# Main.net
KiCad netlist of a schematic drawn in Altium Designer
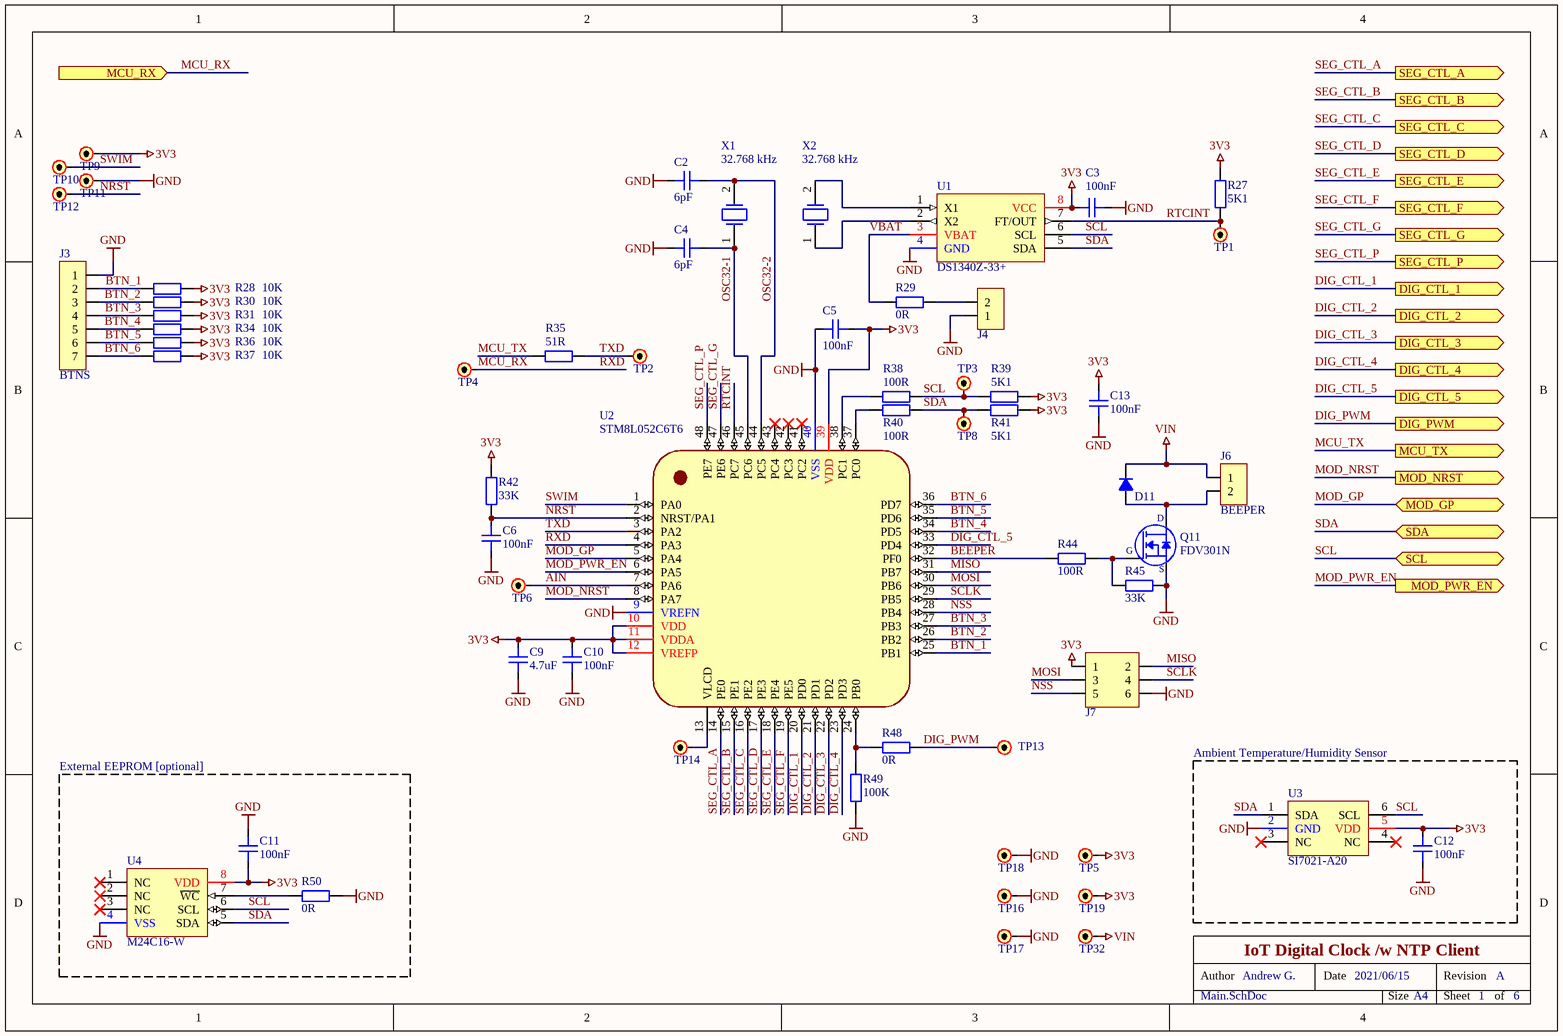
[diagram p0: Main.SchDoc]

(export (version "E")
  (design (tool "Eeschema 10.0.6"))
  (components
    (comp (ref "C2")
      (value "6pF")
      (footprint "0603C_RF_M")
      (description "Capacitor")
      (fields (field (name "TOLERANCE") "?") (field (name "MANUFACTURER") "Generic Brand"))
      (libsource (lib "AG.Generic") (part "C"))
    )
    (comp (ref "C3")
      (value "100nF")
      (footprint "0603C_RF_M")
      (description "Capacitor")
      (fields (field (name "TOLERANCE") "?") (field (name "MANUFACTURER") "Generic Brand"))
      (libsource (lib "AG.Generic") (part "C"))
    )
    (comp (ref "C4")
      (value "6pF")
      (footprint "0603C_RF_M")
      (description "Capacitor")
      (fields (field (name "TOLERANCE") "?") (field (name "MANUFACTURER") "Generic Brand"))
      (libsource (lib "AG.Generic") (part "C"))
    )
    (comp (ref "C5")
      (value "100nF")
      (footprint "0603C_RF_M")
      (description "Capacitor")
      (fields (field (name "TOLERANCE") "?") (field (name "MANUFACTURER") "Generic Brand"))
      (libsource (lib "AG.Generic") (part "C"))
    )
    (comp (ref "C6")
      (value "100nF")
      (footprint "0603C_RF_M")
      (description "Capacitor")
      (fields (field (name "TOLERANCE") "?") (field (name "MANUFACTURER") "Generic Brand"))
      (libsource (lib "AG.Generic") (part "C"))
    )
    (comp (ref "C9")
      (value "4.7uF")
      (footprint "0603C_RF_M")
      (description "Capacitor")
      (fields (field (name "TOLERANCE") "?") (field (name "MANUFACTURER") "Generic Brand"))
      (libsource (lib "AG.Generic") (part "C"))
    )
    (comp (ref "C10")
      (value "100nF")
      (footprint "0603C_RF_M")
      (description "Capacitor")
      (fields (field (name "TOLERANCE") "?") (field (name "MANUFACTURER") "Generic Brand"))
      (libsource (lib "AG.Generic") (part "C"))
    )
    (comp (ref "C11")
      (value "100nF")
      (footprint "0603C_RF_M")
      (description "Capacitor")
      (fields (field (name "TOLERANCE") "?") (field (name "MANUFACTURER") "Generic Brand"))
      (libsource (lib "AG.Generic") (part "C"))
    )
    (comp (ref "C12")
      (value "100nF")
      (footprint "0603C_RF_M")
      (description "Capacitor")
      (fields (field (name "TOLERANCE") "?") (field (name "MANUFACTURER") "Generic Brand"))
      (libsource (lib "AG.Generic") (part "C"))
    )
    (comp (ref "C13")
      (value "100nF")
      (footprint "0805C_RF_M")
      (description "Capacitor")
      (fields (field (name "TOLERANCE") "?") (field (name "MANUFACTURER") "Generic Brand"))
      (libsource (lib "AG.Generic") (part "C"))
    )
    (comp (ref "D11")
      (value "D")
      (footprint "ONSEMI_DO214AC_RF_M")
      (description "Diode (Rectifier)")
      (fields (field (name "MANUFACTURER") "Generic Brand"))
      (libsource (lib "AG.Generic") (part "D"))
    )
    (comp (ref "J3")
      (value "BTNS")
      (footprint "HEADER-2.54-7P1")
      (description "Pin Header Single Row 7 Positions")
      (libsource (lib "AG.Connectors") (part "PINHDR-7P1"))
    )
    (comp (ref "J4")
      (value "PINHDR-2P1")
      (footprint "HEADER-2.54-2P1")
      (description "Pin Header Single Row 2 Positions")
      (libsource (lib "") (part "PINHDR-2P1_1"))
    )
    (comp (ref "J6")
      (value "BEEPER")
      (footprint "HEADER-2.54-2P1")
      (description "Pin Header Single Row 2 Positions")
      (libsource (lib "AG.Connectors") (part "PINHDR-2P1"))
    )
    (comp (ref "J7")
      (value "PINHDR-6P2-2.54")
      (footprint "HEADER-2.54-6P-2R")
      (description "Rectangular Pin Header 6 Positions 2 Rows")
      (libsource (lib "AG.Connectors") (part "PINHDR-6P2-2.54"))
    )
    (comp (ref "Q11")
      (value "FDV301N")
      (footprint "IRLML_SOT-23")
      (description "MOSFET N-CH 25V 220MA SOT23")
      (fields
        (field (name "MANUFACTURER") "ON Semiconductor")
        (field (name "ALTERNATIVE SUPPLIER PART NO") "9010000157")
      )
      (libsource (lib "AG.Discrete") (part "FDV301N"))
    )
    (comp (ref "R27")
      (value "5K1")
      (footprint "0603R_RF_M")
      (description "Resistor")
      (fields (field (name "TOLERANCE") "?") (field (name "MANUFACTURER") "Generic Brand"))
      (libsource (lib "AG.Generic") (part "R"))
    )
    (comp (ref "R28")
      (value "10K")
      (footprint "0603R_RF_M")
      (description "Resistor")
      (fields (field (name "TOLERANCE") "?") (field (name "MANUFACTURER") "Generic Brand"))
      (libsource (lib "AG.Generic") (part "R"))
    )
    (comp (ref "R29")
      (value "0R")
      (footprint "0805R_RF_M")
      (description "Resistor")
      (fields (field (name "TOLERANCE") "?") (field (name "MANUFACTURER") "Generic Brand"))
      (libsource (lib "") (part "R_1"))
    )
    (comp (ref "R30")
      (value "10K")
      (footprint "0603R_RF_M")
      (description "Resistor")
      (fields (field (name "TOLERANCE") "?") (field (name "MANUFACTURER") "Generic Brand"))
      (libsource (lib "AG.Generic") (part "R"))
    )
    (comp (ref "R31")
      (value "10K")
      (footprint "0603R_RF_M")
      (description "Resistor")
      (fields (field (name "TOLERANCE") "?") (field (name "MANUFACTURER") "Generic Brand"))
      (libsource (lib "AG.Generic") (part "R"))
    )
    (comp (ref "R34")
      (value "10K")
      (footprint "0603R_RF_M")
      (description "Resistor")
      (fields (field (name "TOLERANCE") "?") (field (name "MANUFACTURER") "Generic Brand"))
      (libsource (lib "AG.Generic") (part "R"))
    )
    (comp (ref "R35")
      (value "51R")
      (footprint "0603R_RF_M")
      (description "Resistor")
      (fields (field (name "TOLERANCE") "?") (field (name "MANUFACTURER") "Generic Brand"))
      (libsource (lib "AG.Generic") (part "R"))
    )
    (comp (ref "R36")
      (value "10K")
      (footprint "0603R_RF_M")
      (description "Resistor")
      (fields (field (name "TOLERANCE") "?") (field (name "MANUFACTURER") "Generic Brand"))
      (libsource (lib "AG.Generic") (part "R"))
    )
    (comp (ref "R37")
      (value "10K")
      (footprint "0603R_RF_M")
      (description "Resistor")
      (fields (field (name "TOLERANCE") "?") (field (name "MANUFACTURER") "Generic Brand"))
      (libsource (lib "AG.Generic") (part "R"))
    )
    (comp (ref "R38")
      (value "100R")
      (footprint "0603R_RF_M")
      (description "Resistor")
      (fields (field (name "TOLERANCE") "?") (field (name "MANUFACTURER") "Generic Brand"))
      (libsource (lib "AG.Generic") (part "R"))
    )
    (comp (ref "R39")
      (value "5K1")
      (footprint "0805R_RF_M")
      (description "Resistor")
      (fields (field (name "TOLERANCE") "?") (field (name "MANUFACTURER") "Generic Brand"))
      (libsource (lib "") (part "R_1"))
    )
    (comp (ref "R40")
      (value "100R")
      (footprint "0603R_RF_M")
      (description "Resistor")
      (fields (field (name "TOLERANCE") "?") (field (name "MANUFACTURER") "Generic Brand"))
      (libsource (lib "AG.Generic") (part "R"))
    )
    (comp (ref "R41")
      (value "5K1")
      (footprint "0805R_RF_M")
      (description "Resistor")
      (fields (field (name "TOLERANCE") "?") (field (name "MANUFACTURER") "Generic Brand"))
      (libsource (lib "") (part "R_1"))
    )
    (comp (ref "R42")
      (value "33K")
      (footprint "0603R_RF_M")
      (description "Resistor")
      (fields (field (name "TOLERANCE") "?") (field (name "MANUFACTURER") "Generic Brand"))
      (libsource (lib "AG.Generic") (part "R"))
    )
    (comp (ref "R44")
      (value "100R")
      (footprint "0805R_RF_M")
      (description "Resistor")
      (fields (field (name "TOLERANCE") "?") (field (name "MANUFACTURER") "Generic Brand"))
      (libsource (lib "") (part "R_1"))
    )
    (comp (ref "R45")
      (value "33K")
      (footprint "0805R_RF_M")
      (description "Resistor")
      (fields (field (name "TOLERANCE") "?") (field (name "MANUFACTURER") "Generic Brand"))
      (libsource (lib "") (part "R_1"))
    )
    (comp (ref "R48")
      (value "0R")
      (footprint "0603R_RF_M")
      (description "Resistor")
      (fields (field (name "TOLERANCE") "?") (field (name "MANUFACTURER") "Generic Brand"))
      (libsource (lib "AG.Generic") (part "R"))
    )
    (comp (ref "R49")
      (value "100K")
      (footprint "0603R_RF_M")
      (description "Resistor")
      (fields (field (name "TOLERANCE") "?") (field (name "MANUFACTURER") "Generic Brand"))
      (libsource (lib "AG.Generic") (part "R"))
    )
    (comp (ref "R50")
      (value "0R")
      (footprint "0603R_RF_M")
      (description "Resistor")
      (fields (field (name "TOLERANCE") "?") (field (name "MANUFACTURER") "Generic Brand"))
      (libsource (lib "AG.Generic") (part "R"))
    )
    (comp (ref "TP1")
      (value "RTCINT")
      (footprint "PAD_R_1MM")
      (description "Test Point / Pad")
      (libsource (lib "AG.Misc") (part "Test Point"))
    )
    (comp (ref "TP2")
      (value "MCU_TX")
      (footprint "PAD_R_1MM")
      (description "Test Point / Pad")
      (libsource (lib "AG.Misc") (part "Test Point"))
    )
    (comp (ref "TP3")
      (value "SCL")
      (footprint "PAD_R_1MM")
      (description "Test Point / Pad")
      (libsource (lib "AG.Misc") (part "Test Point"))
    )
    (comp (ref "TP4")
      (value "MCU_RX")
      (footprint "PAD_R_1MM")
      (description "Test Point / Pad")
      (libsource (lib "AG.Misc") (part "Test Point"))
    )
    (comp (ref "TP5")
      (value "3V3")
      (footprint "PAD_R_1.5MM")
      (description "Test Point / Pad")
      (libsource (lib "AG.Misc") (part "Test Point"))
    )
    (comp (ref "TP6")
      (value "3V3")
      (footprint "PAD_R_1MM")
      (description "Test Point / Pad")
      (libsource (lib "AG.Misc") (part "Test Point"))
    )
    (comp (ref "TP8")
      (value "SDA")
      (footprint "PAD_R_1MM")
      (description "Test Point / Pad")
      (libsource (lib "AG.Misc") (part "Test Point"))
    )
    (comp (ref "TP9")
      (value "VDD")
      (footprint "PAD_R_1MM")
      (description "Test Point / Pad")
      (libsource (lib "AG.Misc") (part "Test Point"))
    )
    (comp (ref "TP10")
      (value "SWIM")
      (footprint "PAD_R_1MM")
      (description "Test Point / Pad")
      (libsource (lib "AG.Misc") (part "Test Point"))
    )
    (comp (ref "TP11")
      (value "GND")
      (footprint "PAD_R_1MM")
      (description "Test Point / Pad")
      (libsource (lib "AG.Misc") (part "Test Point"))
    )
    (comp (ref "TP12")
      (value "NRST")
      (footprint "PAD_R_1MM")
      (description "Test Point / Pad")
      (libsource (lib "AG.Misc") (part "Test Point"))
    )
    (comp (ref "TP13")
      (value "PWM")
      (footprint "PAD_R_1MM")
      (description "Test Point / Pad")
      (libsource (lib "AG.Misc") (part "Test Point"))
    )
    (comp (ref "TP14")
      (value "VLCD")
      (footprint "PAD_R_1MM")
      (description "Test Point / Pad")
      (libsource (lib "AG.Misc") (part "Test Point"))
    )
    (comp (ref "TP16")
      (value "GND")
      (footprint "PAD_R_1.5MM")
      (description "Test Point / Pad")
      (libsource (lib "AG.Misc") (part "Test Point"))
    )
    (comp (ref "TP17")
      (value "GND")
      (footprint "PAD_R_1.5MM")
      (description "Test Point / Pad")
      (libsource (lib "AG.Misc") (part "Test Point"))
    )
    (comp (ref "TP18")
      (value "GND")
      (footprint "PAD_R_1.5MM")
      (description "Test Point / Pad")
      (libsource (lib "AG.Misc") (part "Test Point"))
    )
    (comp (ref "TP19")
      (value "3V3")
      (footprint "PAD_R_1.5MM")
      (description "Test Point / Pad")
      (libsource (lib "AG.Misc") (part "Test Point"))
    )
    (comp (ref "TP32")
      (value "VIN")
      (footprint "PAD_R_1.5MM")
      (description "Test Point / Pad")
      (libsource (lib "AG.Misc") (part "Test Point"))
    )
    (comp (ref "U1")
      (value "DS1340Z-33+")
      (footprint "SOIC-8")
      (description "IC RTC CLK/CALENDAR I2C 8-SOIC")
      (fields
        (field (name "MANUFACTURER") "Maxim Integrated")
        (field (name "ALTERNATIVE SUPPLIER PART NO") "9000387657")
      )
      (libsource (lib "AG.IC") (part "DS1340Z-33+"))
    )
    (comp (ref "U2")
      (value "STM8L052C6T6")
      (footprint "ST_LQFP-48")
      (description "IC MCU 8BIT 32KB FLASH 48LQFP")
      (fields (field (name "MANUFACTURER") "STMicroelectronics"))
      (libsource (lib "AG.MCU") (part "STM8L052C6T6"))
    )
    (comp (ref "U3")
      (value "SI7021-A20")
      (footprint "SI7021_DFN-6_RF_M")
      (description "SENS HUMID/TEMP 3.6V I2C 2% 6DFN")
      (fields (field (name "MANUFACTURER") "Silicon Labs"))
      (libsource (lib "AG.IC") (part "SI7021-A20"))
    )
    (comp (ref "U4")
      (value "M24C16-W")
      (footprint "SOIC-8")
      (description "IC SRL EEPROM 16KBIT 2.5V 8-SOIC")
      (fields (field (name "MANUFACTURER") "STMicroelectronics"))
      (libsource (lib "AG.IC") (part "M24C16-W"))
    )
    (comp (ref "X1")
      (value "32.768 kHz")
      (footprint "XTAL_3215")
      (description "Crystal Resonator (2 Leads)")
      (fields (field (name "MANUFACTURER") "Geyer") (field (name "MANUFACTURER PART NO") "KX-327NHT"))
      (libsource (lib "AG.Passive") (part "KX-327NHT"))
    )
    (comp (ref "X2")
      (value "32.768 kHz")
      (footprint "XTAL_3215")
      (description "Crystal Resonator (2 Leads)")
      (fields (field (name "MANUFACTURER") "Geyer") (field (name "MANUFACTURER PART NO") "KX-327NHT"))
      (libsource (lib "AG.Passive") (part "KX-327NHT"))
    )
  )
  (nets
    (net (code "1") (name "/AIN") (class "Default")
      (node (ref "TP6") (pin "1") (pinfunction "1_1") (pintype "passive"))
      (node (ref "U2") (pin "7") (pinfunction "PA6_7") (pintype "bidirectional"))
    )
    (net (code "2") (name "/BEEPER") (class "Default")
      (node (ref "R44") (pin "1") (pintype "passive"))
      (node (ref "U2") (pin "32") (pinfunction "PF0_32") (pintype "bidirectional"))
    )
    (net (code "3") (name "/BTN_1") (class "Default")
      (node (ref "J3") (pin "2") (pinfunction "2_2") (pintype "passive"))
      (node (ref "R28") (pin "1") (pintype "passive"))
      (node (ref "U2") (pin "25") (pinfunction "PB1_25") (pintype "bidirectional"))
    )
    (net (code "4") (name "/BTN_2") (class "Default")
      (node (ref "J3") (pin "3") (pinfunction "3_3") (pintype "passive"))
      (node (ref "R30") (pin "1") (pintype "passive"))
      (node (ref "U2") (pin "26") (pinfunction "PB2_26") (pintype "bidirectional"))
    )
    (net (code "5") (name "/BTN_3") (class "Default")
      (node (ref "J3") (pin "4") (pinfunction "4_4") (pintype "passive"))
      (node (ref "R31") (pin "1") (pintype "passive"))
      (node (ref "U2") (pin "27") (pinfunction "PB3_27") (pintype "bidirectional"))
    )
    (net (code "6") (name "/BTN_4") (class "Default")
      (node (ref "J3") (pin "5") (pinfunction "5_5") (pintype "passive"))
      (node (ref "R34") (pin "1") (pintype "passive"))
      (node (ref "U2") (pin "34") (pinfunction "PD5_34") (pintype "bidirectional"))
    )
    (net (code "7") (name "/BTN_5") (class "Default")
      (node (ref "J3") (pin "6") (pinfunction "6_6") (pintype "passive"))
      (node (ref "R36") (pin "1") (pintype "passive"))
      (node (ref "U2") (pin "35") (pinfunction "PD6_35") (pintype "bidirectional"))
    )
    (net (code "8") (name "/BTN_6") (class "Default")
      (node (ref "J3") (pin "7") (pinfunction "7_7") (pintype "passive"))
      (node (ref "R37") (pin "1") (pintype "passive"))
      (node (ref "U2") (pin "36") (pinfunction "PD7_36") (pintype "bidirectional"))
    )
    (net (code "9") (name "/DIG_CTL_1") (class "Default")
      (node (ref "U2") (pin "20") (pinfunction "PD0_20") (pintype "bidirectional"))
    )
    (net (code "10") (name "/DIG_CTL_2") (class "Default")
      (node (ref "U2") (pin "21") (pinfunction "PD1_21") (pintype "bidirectional"))
    )
    (net (code "11") (name "/DIG_CTL_3") (class "Default")
      (node (ref "U2") (pin "22") (pinfunction "PD2_22") (pintype "bidirectional"))
    )
    (net (code "12") (name "/DIG_CTL_4") (class "Default")
      (node (ref "U2") (pin "23") (pinfunction "PD3_23") (pintype "bidirectional"))
    )
    (net (code "13") (name "/DIG_CTL_5") (class "Default")
      (node (ref "U2") (pin "33") (pinfunction "PD4_33") (pintype "bidirectional"))
    )
    (net (code "14") (name "/DIG_PWM") (class "Default")
      (node (ref "R48") (pin "1") (pintype "passive"))
      (node (ref "TP13") (pin "1") (pinfunction "1_1") (pintype "passive"))
    )
    (net (code "15") (name "/MCU_RX") (class "Default")
      (node (ref "TP4") (pin "1") (pinfunction "1_1") (pintype "passive"))
      (node (ref "U2") (pin "4") (pinfunction "PA3_4") (pintype "bidirectional"))
    )
    (net (code "16") (name "/MCU_TX") (class "Default") (node (ref "R35") (pin "1") (pintype "passive")))
    (net (code "17") (name "/MISO") (class "Default")
      (node (ref "J7") (pin "2") (pinfunction "2_2") (pintype "passive"))
      (node (ref "U2") (pin "31") (pinfunction "PB7_31") (pintype "bidirectional"))
    )
    (net (code "18") (name "/MOD_GP") (class "Default")
      (node (ref "U2") (pin "5") (pinfunction "PA4_5") (pintype "bidirectional"))
    )
    (net (code "19") (name "/MOD_NRST") (class "Default")
      (node (ref "U2") (pin "8") (pinfunction "PA7_8") (pintype "bidirectional"))
    )
    (net (code "20") (name "/MOD_PWR_EN") (class "Default")
      (node (ref "U2") (pin "6") (pinfunction "PA5_6") (pintype "bidirectional"))
    )
    (net (code "21") (name "/MOSI") (class "Default")
      (node (ref "J7") (pin "3") (pinfunction "3_3") (pintype "passive"))
      (node (ref "U2") (pin "30") (pinfunction "PB6_30") (pintype "bidirectional"))
    )
    (net (code "22") (name "/NRST") (class "Default")
      (node (ref "C6") (pin "2") (pinfunction "2_2") (pintype "passive"))
      (node (ref "R42") (pin "1") (pintype "passive"))
      (node (ref "TP12") (pin "1") (pinfunction "1_1") (pintype "passive"))
      (node (ref "U2") (pin "2") (pinfunction "NRST/PA1_2") (pintype "bidirectional"))
    )
    (net (code "23") (name "/NSS") (class "Default")
      (node (ref "J7") (pin "5") (pinfunction "5_5") (pintype "passive"))
      (node (ref "U2") (pin "28") (pinfunction "PB4_28") (pintype "bidirectional"))
    )
    (net (code "24") (name "/OSC32-1") (class "Default")
      (node (ref "C4") (pin "1") (pinfunction "1_1") (pintype "passive"))
      (node (ref "U2") (pin "45") (pinfunction "PC6_45") (pintype "bidirectional"))
      (node (ref "X1") (pin "1") (pinfunction "1_1") (pintype "passive"))
    )
    (net (code "25") (name "/OSC32-2") (class "Default")
      (node (ref "C2") (pin "1") (pinfunction "1_1") (pintype "passive"))
      (node (ref "U2") (pin "44") (pinfunction "PC5_44") (pintype "bidirectional"))
      (node (ref "X1") (pin "2") (pinfunction "2_2") (pintype "passive"))
    )
    (net (code "26") (name "/RTCINT") (class "Default")
      (node (ref "R27") (pin "1") (pintype "passive"))
      (node (ref "TP1") (pin "1") (pinfunction "1_1") (pintype "passive"))
      (node (ref "U1") (pin "7") (pinfunction "FT/OUT_7") (pintype "output"))
      (node (ref "U2") (pin "46") (pinfunction "PC7_46") (pintype "bidirectional"))
    )
    (net (code "27") (name "/SCL") (class "Default")
      (node (ref "R38") (pin "2") (pintype "passive"))
      (node (ref "R39") (pin "1") (pintype "passive"))
      (node (ref "TP3") (pin "1") (pinfunction "1_1") (pintype "passive"))
      (node (ref "U1") (pin "6") (pinfunction "SCL_6") (pintype "open_collector"))
      (node (ref "U3") (pin "6") (pinfunction "SCL_6") (pintype "passive"))
      (node (ref "U4") (pin "6") (pinfunction "SCL_6") (pintype "bidirectional"))
    )
    (net (code "28") (name "/SCLK") (class "Default")
      (node (ref "J7") (pin "4") (pinfunction "4_4") (pintype "passive"))
      (node (ref "U2") (pin "29") (pinfunction "PB5_29") (pintype "bidirectional"))
    )
    (net (code "29") (name "/SDA") (class "Default")
      (node (ref "R40") (pin "2") (pintype "passive"))
      (node (ref "R41") (pin "1") (pintype "passive"))
      (node (ref "TP8") (pin "1") (pinfunction "1_1") (pintype "passive"))
      (node (ref "U1") (pin "5") (pinfunction "SDA_5") (pintype "open_collector"))
      (node (ref "U3") (pin "1") (pinfunction "SDA_1") (pintype "passive"))
      (node (ref "U4") (pin "5") (pinfunction "SDA_5") (pintype "bidirectional"))
    )
    (net (code "30") (name "/SEG_CTL_A") (class "Default")
      (node (ref "U2") (pin "14") (pinfunction "PE0_14") (pintype "bidirectional"))
    )
    (net (code "31") (name "/SEG_CTL_B") (class "Default")
      (node (ref "U2") (pin "15") (pinfunction "PE1_15") (pintype "bidirectional"))
    )
    (net (code "32") (name "/SEG_CTL_C") (class "Default")
      (node (ref "U2") (pin "16") (pinfunction "PE2_16") (pintype "bidirectional"))
    )
    (net (code "33") (name "/SEG_CTL_D") (class "Default")
      (node (ref "U2") (pin "17") (pinfunction "PE3_17") (pintype "bidirectional"))
    )
    (net (code "34") (name "/SEG_CTL_E") (class "Default")
      (node (ref "U2") (pin "18") (pinfunction "PE4_18") (pintype "bidirectional"))
    )
    (net (code "35") (name "/SEG_CTL_F") (class "Default")
      (node (ref "U2") (pin "19") (pinfunction "PE5_19") (pintype "bidirectional"))
    )
    (net (code "36") (name "/SEG_CTL_G") (class "Default")
      (node (ref "U2") (pin "47") (pinfunction "PE6_47") (pintype "bidirectional"))
    )
    (net (code "37") (name "/SEG_CTL_P") (class "Default")
      (node (ref "U2") (pin "48") (pinfunction "PE7_48") (pintype "bidirectional"))
    )
    (net (code "38") (name "/SWIM") (class "Default")
      (node (ref "TP10") (pin "1") (pinfunction "1_1") (pintype "passive"))
      (node (ref "U2") (pin "1") (pinfunction "PA0_1") (pintype "bidirectional"))
    )
    (net (code "39") (name "/TXD") (class "Default")
      (node (ref "R35") (pin "2") (pintype "passive"))
      (node (ref "TP2") (pin "1") (pinfunction "1_1") (pintype "passive"))
      (node (ref "U2") (pin "3") (pinfunction "PA2_3") (pintype "bidirectional"))
    )
    (net (code "40") (name "/VBAT") (class "Default")
      (node (ref "R29") (pin "2") (pintype "passive"))
      (node (ref "U1") (pin "3") (pinfunction "VBAT_3") (pintype "power_in"))
    )
    (net (code "41") (name "3V3") (class "Default")
      (node (ref "C10") (pin "2") (pinfunction "2_2") (pintype "passive"))
      (node (ref "C11") (pin "2") (pinfunction "2_2") (pintype "passive"))
      (node (ref "C12") (pin "2") (pinfunction "2_2") (pintype "passive"))
      (node (ref "C13") (pin "2") (pinfunction "2_2") (pintype "passive"))
      (node (ref "C3") (pin "2") (pinfunction "2_2") (pintype "passive"))
      (node (ref "C5") (pin "1") (pinfunction "1_1") (pintype "passive"))
      (node (ref "C9") (pin "2") (pinfunction "2_2") (pintype "passive"))
      (node (ref "J7") (pin "1") (pinfunction "1_1") (pintype "passive"))
      (node (ref "R27") (pin "2") (pintype "passive"))
      (node (ref "R28") (pin "2") (pintype "passive"))
      (node (ref "R30") (pin "2") (pintype "passive"))
      (node (ref "R31") (pin "2") (pintype "passive"))
      (node (ref "R34") (pin "2") (pintype "passive"))
      (node (ref "R36") (pin "2") (pintype "passive"))
      (node (ref "R37") (pin "2") (pintype "passive"))
      (node (ref "R39") (pin "2") (pintype "passive"))
      (node (ref "R41") (pin "2") (pintype "passive"))
      (node (ref "R42") (pin "2") (pintype "passive"))
      (node (ref "TP19") (pin "1") (pinfunction "1_1") (pintype "passive"))
      (node (ref "TP5") (pin "1") (pinfunction "1_1") (pintype "passive"))
      (node (ref "TP9") (pin "1") (pinfunction "1_1") (pintype "passive"))
      (node (ref "U1") (pin "8") (pinfunction "VCC_8") (pintype "power_in"))
      (node (ref "U2") (pin "10") (pinfunction "VDD_10") (pintype "power_in"))
      (node (ref "U2") (pin "11") (pinfunction "VDDA_11") (pintype "power_in"))
      (node (ref "U2") (pin "12") (pinfunction "VREFP_12") (pintype "power_in"))
      (node (ref "U2") (pin "39") (pinfunction "VDD_39") (pintype "power_in"))
      (node (ref "U3") (pin "5") (pinfunction "VDD_5") (pintype "passive"))
      (node (ref "U4") (pin "8") (pinfunction "VDD_8") (pintype "power_in"))
    )
    (net (code "42") (name "GND") (class "Default")
      (node (ref "C10") (pin "1") (pinfunction "1_1") (pintype "passive"))
      (node (ref "C11") (pin "1") (pinfunction "1_1") (pintype "passive"))
      (node (ref "C12") (pin "1") (pinfunction "1_1") (pintype "passive"))
      (node (ref "C13") (pin "1") (pinfunction "1_1") (pintype "passive"))
      (node (ref "C2") (pin "2") (pinfunction "2_2") (pintype "passive"))
      (node (ref "C3") (pin "1") (pinfunction "1_1") (pintype "passive"))
      (node (ref "C4") (pin "2") (pinfunction "2_2") (pintype "passive"))
      (node (ref "C5") (pin "2") (pinfunction "2_2") (pintype "passive"))
      (node (ref "C6") (pin "1") (pinfunction "1_1") (pintype "passive"))
      (node (ref "C9") (pin "1") (pinfunction "1_1") (pintype "passive"))
      (node (ref "J3") (pin "1") (pinfunction "1_1") (pintype "passive"))
      (node (ref "J4") (pin "1") (pinfunction "1_1") (pintype "passive"))
      (node (ref "J7") (pin "6") (pinfunction "6_6") (pintype "passive"))
      (node (ref "Q11") (pin "2") (pinfunction "S_2") (pintype "passive"))
      (node (ref "R45") (pin "1") (pintype "passive"))
      (node (ref "R49") (pin "2") (pintype "passive"))
      (node (ref "R50") (pin "2") (pintype "passive"))
      (node (ref "TP11") (pin "1") (pinfunction "1_1") (pintype "passive"))
      (node (ref "TP16") (pin "1") (pinfunction "1_1") (pintype "passive"))
      (node (ref "TP17") (pin "1") (pinfunction "1_1") (pintype "passive"))
      (node (ref "TP18") (pin "1") (pinfunction "1_1") (pintype "passive"))
      (node (ref "U1") (pin "4") (pinfunction "GND_4") (pintype "power_in"))
      (node (ref "U2") (pin "40") (pinfunction "VSS_40") (pintype "power_in"))
      (node (ref "U2") (pin "9") (pinfunction "VREFN_9") (pintype "power_in"))
      (node (ref "U3") (pin "2") (pinfunction "GND_2") (pintype "passive"))
      (node (ref "U4") (pin "4") (pinfunction "VSS_4") (pintype "power_in"))
    )
    (net (code "43") (name "Net-(J4-Pad2)") (class "Default")
      (node (ref "J4") (pin "2") (pinfunction "2_2") (pintype "passive"))
      (node (ref "R29") (pin "1") (pintype "passive"))
    )
    (net (code "44") (name "Net-(Q11-D)") (class "Default")
      (node (ref "D11") (pin "A") (pinfunction "A_A") (pintype "passive"))
      (node (ref "J6") (pin "2") (pinfunction "2_2") (pintype "passive"))
      (node (ref "Q11") (pin "3") (pinfunction "D_3") (pintype "passive"))
    )
    (net (code "45") (name "Net-(Q11-G)") (class "Default")
      (node (ref "Q11") (pin "1") (pinfunction "G_1") (pintype "passive"))
      (node (ref "R44") (pin "2") (pintype "passive"))
      (node (ref "R45") (pin "2") (pintype "passive"))
    )
    (net (code "46") (name "Net-(U1-X1)") (class "Default")
      (node (ref "U1") (pin "1") (pinfunction "X1_1") (pintype "input"))
      (node (ref "X2") (pin "2") (pinfunction "2_2") (pintype "passive"))
    )
    (net (code "47") (name "Net-(U1-X2)") (class "Default")
      (node (ref "U1") (pin "2") (pinfunction "X2_2") (pintype "output"))
      (node (ref "X2") (pin "1") (pinfunction "1_1") (pintype "passive"))
    )
    (net (code "48") (name "Net-(U2-PB0)") (class "Default")
      (node (ref "R48") (pin "2") (pintype "passive"))
      (node (ref "R49") (pin "1") (pintype "passive"))
      (node (ref "U2") (pin "24") (pinfunction "PB0_24") (pintype "bidirectional"))
    )
    (net (code "49") (name "Net-(U2-PC0)") (class "Default")
      (node (ref "R40") (pin "1") (pintype "passive"))
      (node (ref "U2") (pin "37") (pinfunction "PC0_37") (pintype "bidirectional"))
    )
    (net (code "50") (name "Net-(U2-PC1)") (class "Default")
      (node (ref "R38") (pin "1") (pintype "passive"))
      (node (ref "U2") (pin "38") (pinfunction "PC1_38") (pintype "bidirectional"))
    )
    (net (code "51") (name "Net-(U2-VLCD)") (class "Default")
      (node (ref "TP14") (pin "1") (pinfunction "1_1") (pintype "passive"))
      (node (ref "U2") (pin "13") (pinfunction "VLCD_13") (pintype "power_in"))
    )
    (net (code "52") (name "Net-(U4-~{WC})") (class "Default")
      (node (ref "R50") (pin "1") (pintype "passive"))
      (node (ref "U4") (pin "7") (pinfunction "~{WC}_7") (pintype "input"))
    )
    (net (code "53") (name "VIN") (class "Default")
      (node (ref "D11") (pin "C") (pinfunction "C_C") (pintype "passive"))
      (node (ref "J6") (pin "1") (pinfunction "1_1") (pintype "passive"))
      (node (ref "TP32") (pin "1") (pinfunction "1_1") (pintype "passive"))
    )
    (net (code "54") (name "unconnected-(U2-PC2-Pad41)") (class "Default")
      (node (ref "U2") (pin "41") (pinfunction "PC2_41") (pintype "bidirectional+no_connect"))
    )
    (net (code "55") (name "unconnected-(U2-PC3-Pad42)") (class "Default")
      (node (ref "U2") (pin "42") (pinfunction "PC3_42") (pintype "bidirectional+no_connect"))
    )
    (net (code "56") (name "unconnected-(U2-PC4-Pad43)") (class "Default")
      (node (ref "U2") (pin "43") (pinfunction "PC4_43") (pintype "bidirectional+no_connect"))
    )
    (net (code "57") (name "unconnected-(U3-NC-Pad3)") (class "Default")
      (node (ref "U3") (pin "3") (pinfunction "NC_3") (pintype "passive+no_connect"))
    )
    (net (code "58") (name "unconnected-(U3-NC-Pad4)") (class "Default")
      (node (ref "U3") (pin "4") (pinfunction "NC_4") (pintype "passive+no_connect"))
    )
    (net (code "59") (name "unconnected-(U4-NC-Pad1)") (class "Default")
      (node (ref "U4") (pin "1") (pinfunction "NC_1") (pintype "passive+no_connect"))
    )
    (net (code "60") (name "unconnected-(U4-NC-Pad2)") (class "Default")
      (node (ref "U4") (pin "2") (pinfunction "NC_2") (pintype "passive+no_connect"))
    )
    (net (code "61") (name "unconnected-(U4-NC-Pad3)") (class "Default")
      (node (ref "U4") (pin "3") (pinfunction "NC_3") (pintype "passive+no_connect"))
    )
  )
)
